# USB_FS.net
KiCad netlist of a schematic drawn in Altium Designer
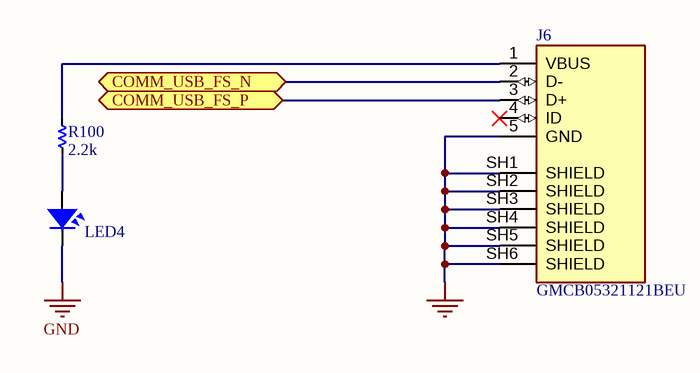
[diagram p0: USB_FS.SchDoc]

(export (version "E")
  (design (tool "Eeschema 10.0.6"))
  (components
    (comp (ref "J6")
      (value "GMCB05321121BEU")
      (footprint "AMPHENOL_GMCB05321121BEU")
      (description "Micro USB 2.0 Type B Receptacle Right Angle SMT, Tape and Reel Packaging")
      (fields (field (name "MF") "Amphenol Commercial Products"))
      (libsource (lib "COMM_SCHLIB") (part "GMCB05321121BEU"))
    )
    (comp (ref "LED4")
      (value "150060RS75000")
      (footprint "LED_0603")
      (libsource (lib "COMM_SCHLIB") (part "LED SMD"))
    )
    (comp (ref "R100")
      (value "2.2k")
      (footprint "RES_C_1608X60")
      (description "RES")
      (libsource (lib "LABLIB") (part "_RES_B_2"))
    )
  )
  (nets
    (net (code "1") (name "/COMM_USB_FS_N") (class "Default")
      (node (ref "J6") (pin "2") (pinfunction "D-_2") (pintype "bidirectional"))
    )
    (net (code "2") (name "/COMM_USB_FS_P") (class "Default")
      (node (ref "J6") (pin "3") (pinfunction "D+_3") (pintype "bidirectional"))
    )
    (net (code "3") (name "GND") (class "Default")
      (node (ref "J6") (pin "5") (pinfunction "GND_5") (pintype "power_in"))
      (node (ref "J6") (pin "SH1") (pinfunction "SHIELD_SH1") (pintype "passive"))
      (node (ref "J6") (pin "SH2") (pinfunction "SHIELD_SH2") (pintype "passive"))
      (node (ref "J6") (pin "SH3") (pinfunction "SHIELD_SH3") (pintype "passive"))
      (node (ref "J6") (pin "SH4") (pinfunction "SHIELD_SH4") (pintype "passive"))
      (node (ref "J6") (pin "SH5") (pinfunction "SHIELD_SH5") (pintype "passive"))
      (node (ref "J6") (pin "SH6") (pinfunction "SHIELD_SH6") (pintype "passive"))
      (node (ref "LED4") (pin "2") (pinfunction "2_2") (pintype "passive"))
    )
    (net (code "4") (name "Net-(J6-VBUS)") (class "Default")
      (node (ref "J6") (pin "1") (pinfunction "VBUS_1") (pintype "power_in"))
      (node (ref "R100") (pin "2") (pinfunction "2_2") (pintype "passive"))
    )
    (net (code "5") (name "Net-(LED4-Pad1)") (class "Default")
      (node (ref "LED4") (pin "1") (pinfunction "1_1") (pintype "passive"))
      (node (ref "R100") (pin "1") (pinfunction "1_1") (pintype "passive"))
    )
    (net (code "6") (name "unconnected-(J6-ID-Pad4)") (class "Default")
      (node (ref "J6") (pin "4") (pinfunction "ID_4") (pintype "bidirectional+no_connect"))
    )
  )
)
